# Diag64Cart.net
KiCad netlist of a schematic drawn in EAGLE
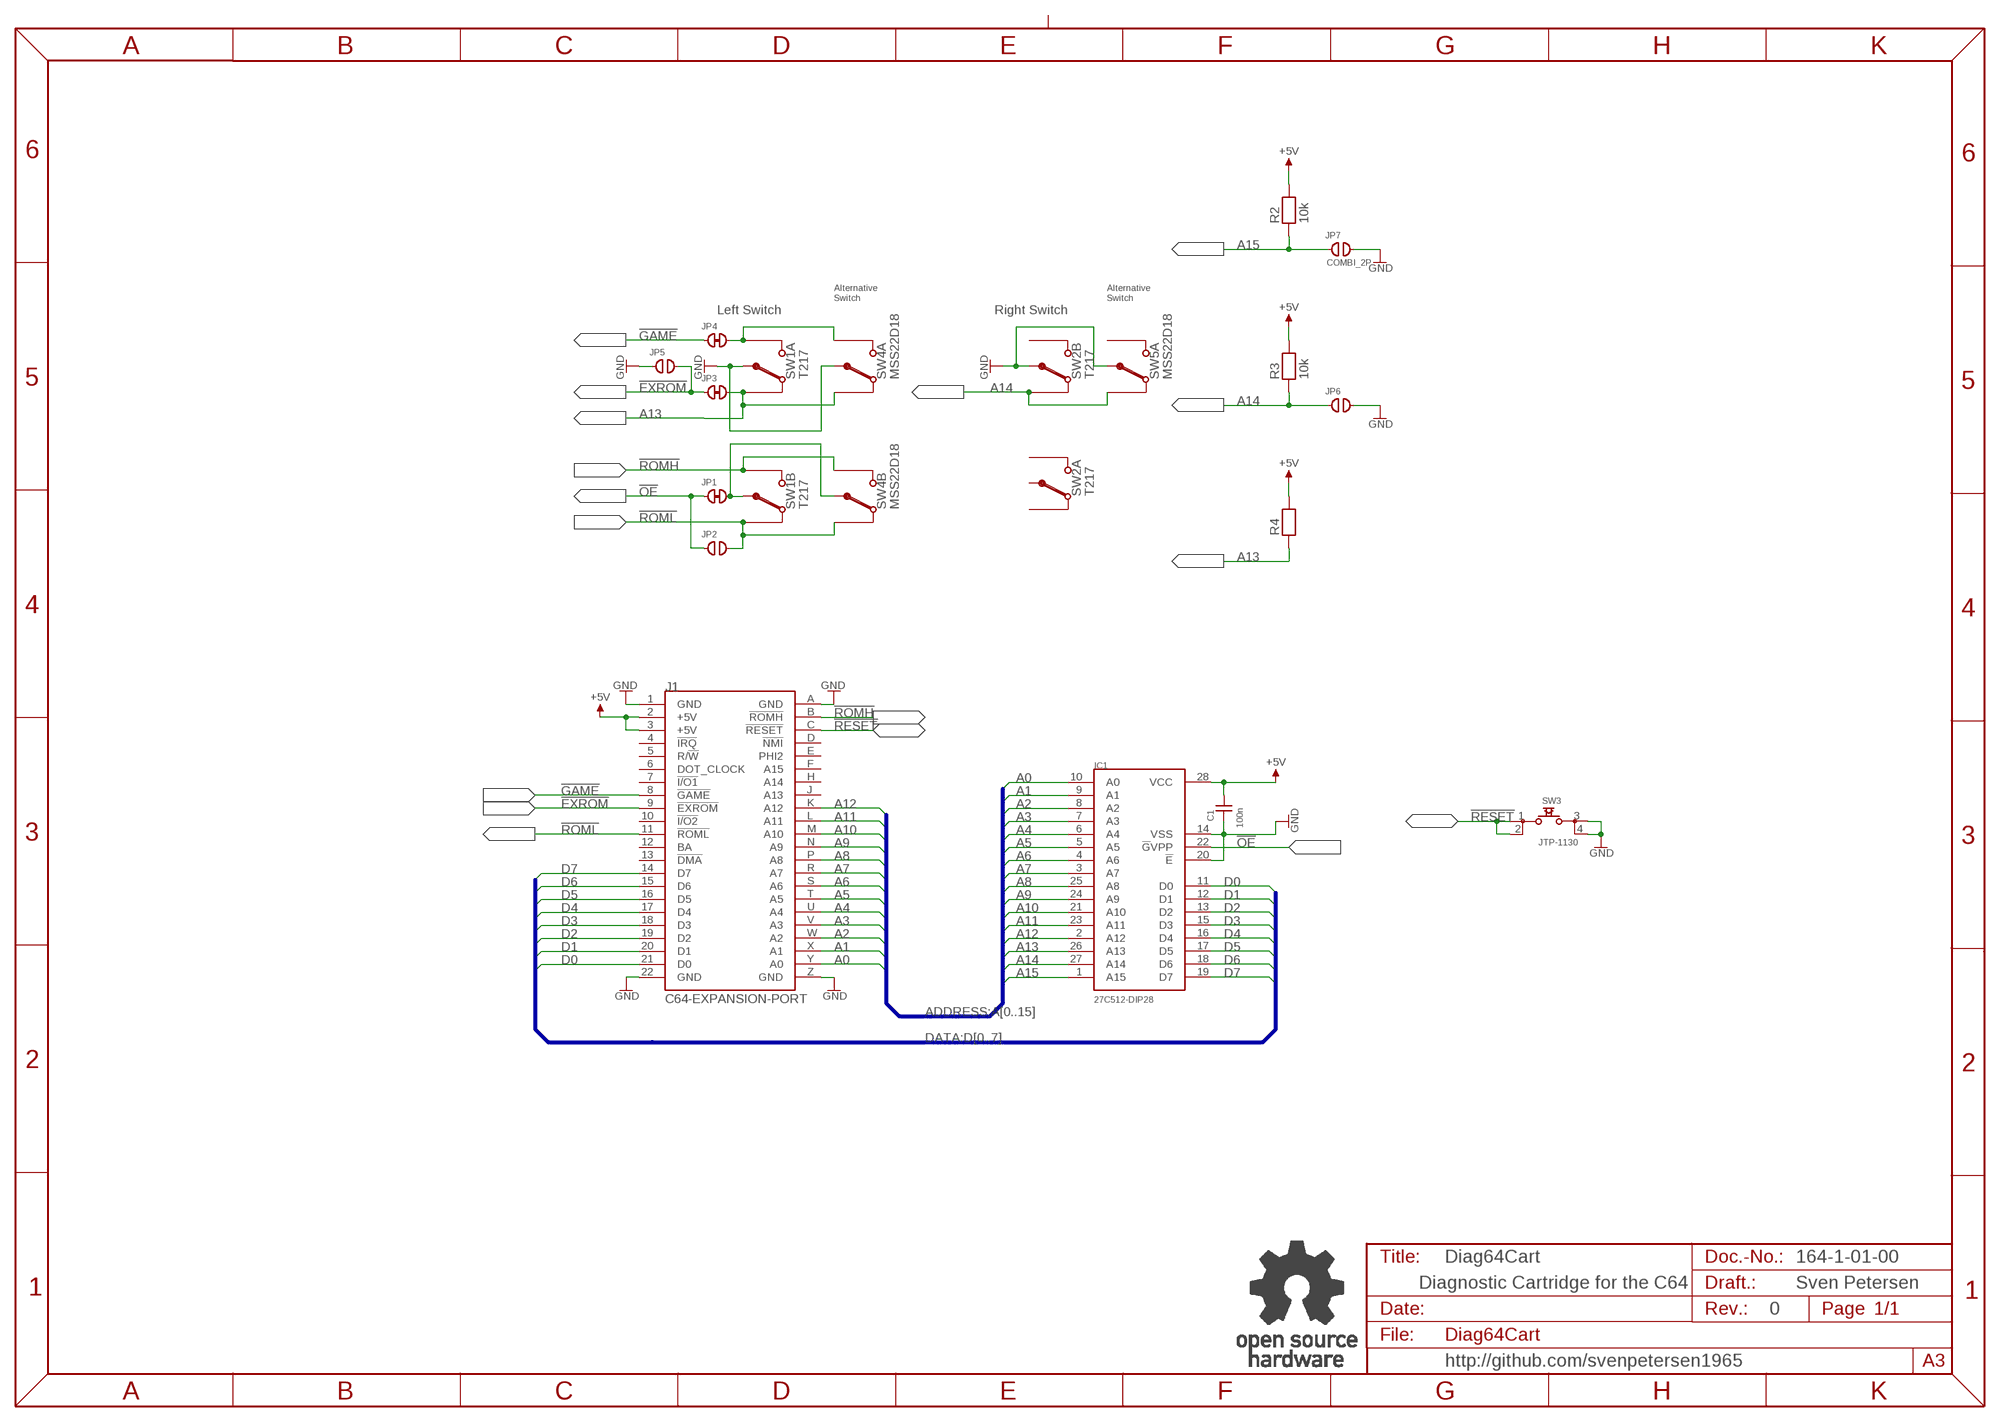
[diagram p0: schematic, sheet 1]

(export (version "E")
  (design (tool "Eeschema 10.0.6"))
  (components
    (comp (ref "C1")
      (value "100n")
      (footprint "eagle-import:C-2,5")
      (libsource (lib "eagle-import") (part "CAP01"))
    )
    (comp (ref "IC1")
      (value "27C512-DIP28")
      (footprint "eagle-import:DIL28-6")
      (libsource (lib "eagle-import") (part "M27C512-DIP28"))
    )
    (comp (ref "J1")
      (value "C64-EXPANSION-PORT")
      (footprint "eagle-import:EXPANSIO_SQ")
      (libsource (lib "eagle-import") (part "C64-EXPANSIONPNARROW"))
    )
    (comp (ref "JP1")
      (value "CLOSED")
      (footprint "eagle-import:CP_CL")
      (libsource (lib "eagle-import") (part "CLOSED"))
    )
    (comp (ref "JP2")
      (value "OPEN")
      (footprint "eagle-import:CP_OP")
      (libsource (lib "eagle-import") (part "OPEN"))
    )
    (comp (ref "JP3")
      (value "CLOSED")
      (footprint "eagle-import:CP_CL")
      (libsource (lib "eagle-import") (part "CLOSED"))
    )
    (comp (ref "JP4")
      (value "CLOSED")
      (footprint "eagle-import:CP_CL")
      (libsource (lib "eagle-import") (part "CLOSED"))
    )
    (comp (ref "JP5")
      (value "OPEN")
      (footprint "eagle-import:CP_OP")
      (libsource (lib "eagle-import") (part "OPEN"))
    )
    (comp (ref "JP6")
      (value "OPEN")
      (footprint "eagle-import:CP_OP")
      (libsource (lib "eagle-import") (part "OPEN"))
    )
    (comp (ref "JP7")
      (value "COMBI_2P")
      (footprint "eagle-import:COMBI-2P")
      (libsource (lib "eagle-import") (part "COMBI_2P"))
    )
    (comp (ref "R2")
      (value "10k")
      (footprint "eagle-import:R-10")
      (libsource (lib "eagle-import") (part "RES04"))
    )
    (comp (ref "R3")
      (value "10k")
      (footprint "eagle-import:R-10")
      (libsource (lib "eagle-import") (part "RES04"))
    )
    (comp (ref "R4")
      (value "10k")
      (footprint "eagle-import:R-10")
      (libsource (lib "eagle-import") (part "RES04"))
    )
    (comp (ref "SW1")
      (value "T217")
      (footprint "eagle-import:T217_SIDE")
      (libsource (lib "eagle-import") (part "T217"))
    )
    (comp (ref "SW2")
      (value "T217")
      (footprint "eagle-import:T217_SIDE")
      (libsource (lib "eagle-import") (part "T217"))
    )
    (comp (ref "SW3")
      (value "JTP-1130")
      (footprint "eagle-import:JTP-1130")
      (libsource (lib "eagle-import") (part "JTP-1130"))
    )
    (comp (ref "SW4")
      (value "MSS22D18")
      (footprint "eagle-import:DPDT_9MM")
      (libsource (lib "eagle-import") (part "DPDT_9MM"))
    )
    (comp (ref "SW5")
      (value "MSS22D18")
      (footprint "eagle-import:DPDT_9MM")
      (libsource (lib "eagle-import") (part "DPDT_9MM"))
    )
    (comp (ref "U$43")
      (value "OPEN_SOURCE_HW")
      (footprint "eagle-import:OPENHW")
      (libsource (lib "eagle-import") (part "OPEN_SOURCE_HW"))
    )
  )
  (nets
    (net (code "25") (name "+5V") (class "Default")
      (node (ref "C1") (pin "2") (pinfunction "2_2") (pintype "passive"))
      (node (ref "IC1") (pin "28") (pinfunction "VCC_28") (pintype "power_in"))
      (node (ref "J1") (pin "2") (pinfunction "+5V_2") (pintype "power_in"))
      (node (ref "J1") (pin "3") (pinfunction "+5V_3") (pintype "power_in"))
      (node (ref "R2") (pin "2") (pinfunction "2_2") (pintype "passive"))
      (node (ref "R3") (pin "2") (pinfunction "2_2") (pintype "passive"))
      (node (ref "R4") (pin "2") (pinfunction "2_2") (pintype "passive"))
    )
    (net (code "26") (name "/A0") (class "Default")
      (node (ref "IC1") (pin "10") (pinfunction "A0_10") (pintype "input"))
      (node (ref "J1") (pin "Y") (pinfunction "A0_Y") (pintype "bidirectional"))
    )
    (net (code "27") (name "/A1") (class "Default")
      (node (ref "IC1") (pin "9") (pinfunction "A1_9") (pintype "input"))
      (node (ref "J1") (pin "X") (pinfunction "A1_X") (pintype "bidirectional"))
    )
    (net (code "28") (name "/A2") (class "Default")
      (node (ref "IC1") (pin "8") (pinfunction "A2_8") (pintype "input"))
      (node (ref "J1") (pin "W") (pinfunction "A2_W") (pintype "bidirectional"))
    )
    (net (code "29") (name "/A3") (class "Default")
      (node (ref "IC1") (pin "7") (pinfunction "A3_7") (pintype "input"))
      (node (ref "J1") (pin "V") (pinfunction "A3_V") (pintype "bidirectional"))
    )
    (net (code "30") (name "/A4") (class "Default")
      (node (ref "IC1") (pin "6") (pinfunction "A4_6") (pintype "input"))
      (node (ref "J1") (pin "U") (pinfunction "A4_U") (pintype "bidirectional"))
    )
    (net (code "31") (name "/A5") (class "Default")
      (node (ref "IC1") (pin "5") (pinfunction "A5_5") (pintype "input"))
      (node (ref "J1") (pin "T") (pinfunction "A5_T") (pintype "bidirectional"))
    )
    (net (code "32") (name "/A6") (class "Default")
      (node (ref "IC1") (pin "4") (pinfunction "A6_4") (pintype "input"))
      (node (ref "J1") (pin "S") (pinfunction "A6_S") (pintype "bidirectional"))
    )
    (net (code "33") (name "/A7") (class "Default")
      (node (ref "IC1") (pin "3") (pinfunction "A7_3") (pintype "input"))
      (node (ref "J1") (pin "R") (pinfunction "A7_R") (pintype "bidirectional"))
    )
    (net (code "34") (name "/A8") (class "Default")
      (node (ref "IC1") (pin "25") (pinfunction "A8_25") (pintype "input"))
      (node (ref "J1") (pin "P") (pinfunction "A8_P") (pintype "bidirectional"))
    )
    (net (code "35") (name "/A9") (class "Default")
      (node (ref "IC1") (pin "24") (pinfunction "A9_24") (pintype "input"))
      (node (ref "J1") (pin "N") (pinfunction "A9_N") (pintype "bidirectional"))
    )
    (net (code "36") (name "/A10") (class "Default")
      (node (ref "IC1") (pin "21") (pinfunction "A10_21") (pintype "input"))
      (node (ref "J1") (pin "M") (pinfunction "A10_M") (pintype "bidirectional"))
    )
    (net (code "37") (name "/A11") (class "Default")
      (node (ref "IC1") (pin "23") (pinfunction "A11_23") (pintype "input"))
      (node (ref "J1") (pin "L") (pinfunction "A11_L") (pintype "bidirectional"))
    )
    (net (code "38") (name "/A12") (class "Default")
      (node (ref "IC1") (pin "2") (pinfunction "A12_2") (pintype "input"))
      (node (ref "J1") (pin "K") (pinfunction "A12_K") (pintype "bidirectional"))
    )
    (net (code "39") (name "/A13") (class "Default")
      (node (ref "IC1") (pin "26") (pinfunction "A13_26") (pintype "input"))
      (node (ref "JP3") (pin "2") (pinfunction "2_2") (pintype "passive"))
      (node (ref "R4") (pin "1") (pinfunction "1_1") (pintype "passive"))
      (node (ref "SW1") (pin "DWN1") (pinfunction "DWN_DWN1") (pintype "bidirectional"))
      (node (ref "SW4") (pin "3") (pinfunction "DWN_3") (pintype "bidirectional"))
    )
    (net (code "40") (name "/A14") (class "Default")
      (node (ref "IC1") (pin "27") (pinfunction "A14_27") (pintype "input"))
      (node (ref "JP6") (pin "1") (pinfunction "1_1") (pintype "passive"))
      (node (ref "R3") (pin "1") (pinfunction "1_1") (pintype "passive"))
      (node (ref "SW2") (pin "DWN2") (pinfunction "DWN_DWN2") (pintype "bidirectional"))
      (node (ref "SW5") (pin "3") (pinfunction "DWN_3") (pintype "bidirectional"))
    )
    (net (code "41") (name "/A15") (class "Default")
      (node (ref "IC1") (pin "1") (pinfunction "A15_1") (pintype "input"))
      (node (ref "JP7") (pin "1") (pinfunction "1_1") (pintype "passive"))
      (node (ref "R2") (pin "1") (pinfunction "1_1") (pintype "passive"))
    )
    (net (code "43") (name "/D0") (class "Default")
      (node (ref "IC1") (pin "11") (pinfunction "D0_11") (pintype "bidirectional"))
      (node (ref "J1") (pin "21") (pinfunction "D0_21") (pintype "bidirectional"))
    )
    (net (code "44") (name "/D1") (class "Default")
      (node (ref "IC1") (pin "12") (pinfunction "D1_12") (pintype "bidirectional"))
      (node (ref "J1") (pin "20") (pinfunction "D1_20") (pintype "bidirectional"))
    )
    (net (code "45") (name "/D2") (class "Default")
      (node (ref "IC1") (pin "13") (pinfunction "D2_13") (pintype "bidirectional"))
      (node (ref "J1") (pin "19") (pinfunction "D2_19") (pintype "bidirectional"))
    )
    (net (code "46") (name "/D3") (class "Default")
      (node (ref "IC1") (pin "15") (pinfunction "D3_15") (pintype "bidirectional"))
      (node (ref "J1") (pin "18") (pinfunction "D3_18") (pintype "bidirectional"))
    )
    (net (code "47") (name "/D4") (class "Default")
      (node (ref "IC1") (pin "16") (pinfunction "D4_16") (pintype "bidirectional"))
      (node (ref "J1") (pin "17") (pinfunction "D4_17") (pintype "bidirectional"))
    )
    (net (code "48") (name "/D5") (class "Default")
      (node (ref "IC1") (pin "17") (pinfunction "D5_17") (pintype "bidirectional"))
      (node (ref "J1") (pin "16") (pinfunction "D5_16") (pintype "bidirectional"))
    )
    (net (code "49") (name "/D6") (class "Default")
      (node (ref "IC1") (pin "18") (pinfunction "D6_18") (pintype "bidirectional"))
      (node (ref "J1") (pin "15") (pinfunction "D6_15") (pintype "bidirectional"))
    )
    (net (code "50") (name "/D7") (class "Default")
      (node (ref "IC1") (pin "19") (pinfunction "D7_19") (pintype "bidirectional"))
      (node (ref "J1") (pin "14") (pinfunction "D7_14") (pintype "bidirectional"))
    )
    (net (code "52") (name "/~{EXROM}") (class "Default")
      (node (ref "J1") (pin "9") (pinfunction "~{EXROM}_9") (pintype "input"))
      (node (ref "JP3") (pin "1") (pinfunction "1_1") (pintype "passive"))
      (node (ref "JP5") (pin "2") (pinfunction "2_2") (pintype "passive"))
    )
    (net (code "53") (name "/~{GAME}") (class "Default")
      (node (ref "J1") (pin "8") (pinfunction "~{GAME}_8") (pintype "input"))
      (node (ref "JP4") (pin "1") (pinfunction "1_1") (pintype "passive"))
    )
    (net (code "54") (name "/~{OE}") (class "Default")
      (node (ref "IC1") (pin "22") (pinfunction "~{G}VPP_22") (pintype "input"))
      (node (ref "JP1") (pin "1") (pinfunction "1_1") (pintype "passive"))
      (node (ref "JP2") (pin "1") (pinfunction "1_1") (pintype "passive"))
    )
    (net (code "55") (name "/~{RESET}") (class "Default")
      (node (ref "J1") (pin "C") (pinfunction "~{RESET}_C") (pintype "open_collector"))
      (node (ref "SW3") (pin "1") (pinfunction "1_1") (pintype "passive"))
      (node (ref "SW3") (pin "2") (pinfunction "2_2") (pintype "passive"))
    )
    (net (code "56") (name "/~{ROMH}") (class "Default")
      (node (ref "J1") (pin "B") (pinfunction "~{ROMH}_B") (pintype "output"))
      (node (ref "SW1") (pin "UP2") (pinfunction "UP_UP2") (pintype "bidirectional"))
      (node (ref "SW4") (pin "6") (pinfunction "UP_6") (pintype "bidirectional"))
    )
    (net (code "57") (name "/~{ROML}") (class "Default")
      (node (ref "J1") (pin "11") (pinfunction "~{ROML}_11") (pintype "output"))
      (node (ref "JP2") (pin "2") (pinfunction "2_2") (pintype "passive"))
      (node (ref "SW1") (pin "DWN2") (pinfunction "DWN_DWN2") (pintype "bidirectional"))
      (node (ref "SW4") (pin "4") (pinfunction "DWN_4") (pintype "bidirectional"))
    )
    (net (code "58") (name "GND") (class "Default")
      (node (ref "C1") (pin "1") (pinfunction "1_1") (pintype "passive"))
      (node (ref "IC1") (pin "14") (pinfunction "VSS_14") (pintype "power_in"))
      (node (ref "IC1") (pin "20") (pinfunction "~{E}_20") (pintype "input"))
      (node (ref "J1") (pin "1") (pinfunction "GND_1") (pintype "power_in"))
      (node (ref "J1") (pin "22") (pinfunction "GND_22") (pintype "power_in"))
      (node (ref "J1") (pin "A") (pinfunction "GND_A") (pintype "power_in"))
      (node (ref "J1") (pin "Z") (pinfunction "GND_Z") (pintype "power_in"))
      (node (ref "JP5") (pin "1") (pinfunction "1_1") (pintype "passive"))
      (node (ref "JP6") (pin "2") (pinfunction "2_2") (pintype "passive"))
      (node (ref "JP7") (pin "2") (pinfunction "2_2") (pintype "passive"))
      (node (ref "SW1") (pin "COM1") (pinfunction "COM_COM1") (pintype "bidirectional"))
      (node (ref "SW2") (pin "COM2") (pinfunction "COM_COM2") (pintype "bidirectional"))
      (node (ref "SW3") (pin "3") (pinfunction "3_3") (pintype "passive"))
      (node (ref "SW3") (pin "4") (pinfunction "4_4") (pintype "passive"))
      (node (ref "SW4") (pin "2") (pinfunction "COM_2") (pintype "bidirectional"))
      (node (ref "SW5") (pin "2") (pinfunction "COM_2") (pintype "bidirectional"))
    )
    (net (code "59") (name "Net-(SW1A-UP)") (class "Default")
      (node (ref "JP4") (pin "2") (pinfunction "2_2") (pintype "passive"))
      (node (ref "SW1") (pin "UP1") (pinfunction "UP_UP1") (pintype "bidirectional"))
      (node (ref "SW4") (pin "1") (pinfunction "UP_1") (pintype "bidirectional"))
    )
    (net (code "60") (name "Net-(SW1B-COM)") (class "Default")
      (node (ref "JP1") (pin "2") (pinfunction "2_2") (pintype "passive"))
      (node (ref "SW1") (pin "COM2") (pinfunction "COM_COM2") (pintype "bidirectional"))
      (node (ref "SW4") (pin "5") (pinfunction "COM_5") (pintype "bidirectional"))
    )
    (net (code "61") (name "unconnected-(J1-A13-PadJ)") (class "Default")
      (node (ref "J1") (pin "J") (pinfunction "A13_J") (pintype "bidirectional"))
    )
    (net (code "62") (name "unconnected-(J1-A14-PadH)") (class "Default")
      (node (ref "J1") (pin "H") (pinfunction "A14_H") (pintype "bidirectional"))
    )
    (net (code "63") (name "unconnected-(J1-A15-PadF)") (class "Default")
      (node (ref "J1") (pin "F") (pinfunction "A15_F") (pintype "bidirectional"))
    )
    (net (code "64") (name "unconnected-(J1-BA-Pad12)") (class "Default")
      (node (ref "J1") (pin "12") (pinfunction "BA_12") (pintype "output"))
    )
    (net (code "65") (name "unconnected-(J1-DOT_CLOCK-Pad6)") (class "Default")
      (node (ref "J1") (pin "6") (pinfunction "DOT_CLOCK_6") (pintype "output"))
    )
    (net (code "66") (name "unconnected-(J1-PHI2-PadE)") (class "Default")
      (node (ref "J1") (pin "E") (pinfunction "PHI2_E") (pintype "output"))
    )
    (net (code "67") (name "unconnected-(J1-R{slash}~{W}-Pad5)") (class "Default")
      (node (ref "J1") (pin "5") (pinfunction "R/~{W}_5") (pintype "output"))
    )
    (net (code "68") (name "unconnected-(J1-~{DMA}-Pad13)") (class "Default")
      (node (ref "J1") (pin "13") (pinfunction "~{DMA}_13") (pintype "input"))
    )
    (net (code "69") (name "unconnected-(J1-~{IRQ}-Pad4)") (class "Default")
      (node (ref "J1") (pin "4") (pinfunction "~{IRQ}_4") (pintype "input"))
    )
    (net (code "70") (name "unconnected-(J1-~{I{slash}O1}-Pad7)") (class "Default")
      (node (ref "J1") (pin "7") (pinfunction "~{I/O1}_7") (pintype "output"))
    )
    (net (code "71") (name "unconnected-(J1-~{I{slash}O2}-Pad10)") (class "Default")
      (node (ref "J1") (pin "10") (pinfunction "~{I/O2}_10") (pintype "output"))
    )
    (net (code "72") (name "unconnected-(J1-~{NMI}-PadD)") (class "Default")
      (node (ref "J1") (pin "D") (pinfunction "~{NMI}_D") (pintype "input"))
    )
    (net (code "73") (name "unconnected-(SW2A-COM-PadCOM1)") (class "Default")
      (node (ref "SW2") (pin "COM1") (pinfunction "COM_COM1") (pintype "bidirectional"))
    )
    (net (code "74") (name "unconnected-(SW2A-DWN-PadDWN1)") (class "Default")
      (node (ref "SW2") (pin "DWN1") (pinfunction "DWN_DWN1") (pintype "bidirectional"))
    )
    (net (code "75") (name "unconnected-(SW2A-UP-PadUP1)") (class "Default")
      (node (ref "SW2") (pin "UP1") (pinfunction "UP_UP1") (pintype "bidirectional"))
    )
    (net (code "76") (name "unconnected-(SW2B-UP-PadUP2)") (class "Default")
      (node (ref "SW2") (pin "UP2") (pinfunction "UP_UP2") (pintype "bidirectional"))
    )
    (net (code "77") (name "unconnected-(SW5A-UP-Pad1)") (class "Default")
      (node (ref "SW5") (pin "1") (pinfunction "UP_1") (pintype "bidirectional"))
    )
  )
)
